# MCU.net
KiCad netlist of a schematic drawn in Altium Designer
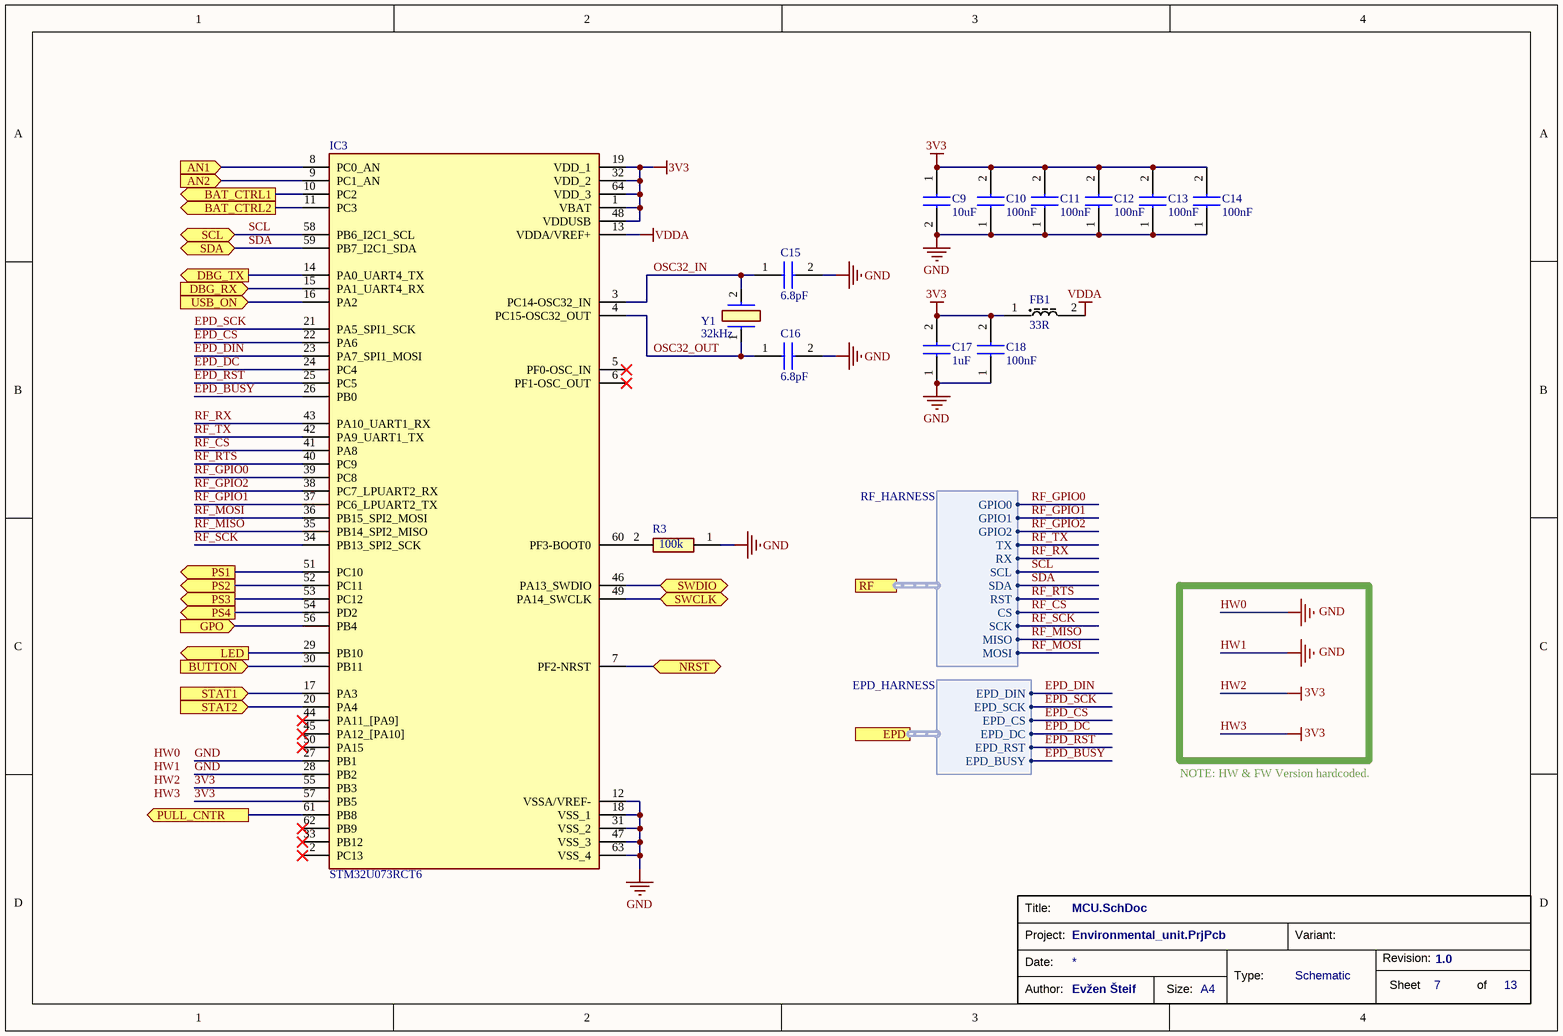
[diagram p0: MCU.SchDoc]

(export (version "E")
  (design (tool "Eeschema 10.0.6"))
  (components
    (comp (ref "C9")
      (value "10uF")
      (footprint "SamacSys:GRM18x")
      (description "Capacitor")
      (fields
        (field (name "MANUFACTURER_PART_NUMBER") "GRM188R61E106KA73D")
        (field (name "MOUSER PART NUMBER") "81-GRM188R61E106KA3D")
      )
      (libsource (lib "*") (part "GRM188R61E106KA73D"))
    )
    (comp (ref "C10")
      (value "100nF")
      (footprint "SamacSys:CAPC1005X70N")
      (description "Capacitor")
      (fields
        (field (name "MANUFACTURER_PART_NUMBER") "GRM155R61A104KA01D")
        (field (name "MOUSER PART NUMBER") "81-GRM155R61A104KA01")
      )
      (libsource (lib "*") (part "GRM155R61A104KA01D"))
    )
    (comp (ref "C11")
      (value "100nF")
      (footprint "SamacSys:CAPC1005X70N")
      (description "Capacitor")
      (fields
        (field (name "MANUFACTURER_PART_NUMBER") "GRM155R61A104KA01D")
        (field (name "MOUSER PART NUMBER") "81-GRM155R61A104KA01")
      )
      (libsource (lib "*") (part "GRM155R61A104KA01D"))
    )
    (comp (ref "C12")
      (value "100nF")
      (footprint "SamacSys:CAPC1005X70N")
      (description "Capacitor")
      (fields
        (field (name "MANUFACTURER_PART_NUMBER") "GRM155R61A104KA01D")
        (field (name "MOUSER PART NUMBER") "81-GRM155R61A104KA01")
      )
      (libsource (lib "*") (part "GRM155R61A104KA01D"))
    )
    (comp (ref "C13")
      (value "100nF")
      (footprint "SamacSys:CAPC1005X70N")
      (description "Capacitor")
      (fields
        (field (name "MANUFACTURER_PART_NUMBER") "GRM155R61A104KA01D")
        (field (name "MOUSER PART NUMBER") "81-GRM155R61A104KA01")
      )
      (libsource (lib "*") (part "GRM155R61A104KA01D"))
    )
    (comp (ref "C14")
      (value "100nF")
      (footprint "SamacSys:CAPC1005X70N")
      (description "Capacitor")
      (fields
        (field (name "MANUFACTURER_PART_NUMBER") "GRM155R61A104KA01D")
        (field (name "MOUSER PART NUMBER") "81-GRM155R61A104KA01")
      )
      (libsource (lib "*") (part "GRM155R61A104KA01D"))
    )
    (comp (ref "C15")
      (value "6.8pF")
      (footprint "SamacSys:GCM155")
      (description "Capacitor")
      (fields
        (field (name "MANUFACTURER_PART_NUMBER") "GCM1555C1H6R8BA16J")
        (field (name "MOUSER PART NUMBER") "81-GCM1555C1H6R8BA6J")
      )
      (libsource (lib "*") (part "GCM1555C1H6R8BA16J"))
    )
    (comp (ref "C16")
      (value "6.8pF")
      (footprint "SamacSys:GCM155")
      (description "Capacitor")
      (fields
        (field (name "MANUFACTURER_PART_NUMBER") "GCM1555C1H6R8BA16J")
        (field (name "MOUSER PART NUMBER") "81-GCM1555C1H6R8BA6J")
      )
      (libsource (lib "*") (part "GCM1555C1H6R8BA16J"))
    )
    (comp (ref "C17")
      (value "1uF")
      (footprint "SamacSys:CAPC1608X90N")
      (description "Capacitor")
      (fields
        (field (name "MANUFACTURER_PART_NUMBER") "GRM188R61A105KA61D")
        (field (name "MOUSER PART NUMBER") "81-GRM39R105K10")
      )
      (libsource (lib "*") (part "GRM188R61A105KA61D"))
    )
    (comp (ref "C18")
      (value "100nF")
      (footprint "SamacSys:CAPC1005X70N")
      (description "Capacitor")
      (fields
        (field (name "MANUFACTURER_PART_NUMBER") "GRM155R61A104KA01D")
        (field (name "MOUSER PART NUMBER") "81-GRM155R61A104KA01")
      )
      (libsource (lib "*") (part "GRM155R61A104KA01D"))
    )
    (comp (ref "FB1")
      (value "33R")
      (footprint "SamacSys:BLM18SP221SN1B")
      (description "Ferrite Bead")
      (fields
        (field (name "MANUFACTURER_PART_NUMBER") "BLM18SG330SN1D")
        (field (name "MOUSER PART NUMBER") "81-BLM18SG330SN1D")
      )
      (libsource (lib "SamacSys") (part "BLM18SG330SN1D"))
    )
    (comp (ref "IC3")
      (value "STM32U073RCT6")
      (footprint "SamacSys:QFP50P1200X1200X160-64N")
      (description "Integrated Circuit")
      (libsource (lib "SamacSys") (part "STM32U073RCT6"))
    )
    (comp (ref "R3")
      (value "100k")
      (footprint "SamacSys:RESC1005X35N")
      (description "Resistor")
      (fields
        (field (name "MANUFACTURER_PART_NUMBER") "RT0402FRE07100KL")
        (field (name "MOUSER PART NUMBER") "603-RT0402FRE07100KL")
      )
      (libsource (lib "*") (part "RT0402FRE07100KL"))
    )
    (comp (ref "Y1")
      (value "32kHz")
      (footprint "SamacSys:ECS32712534RRTR")
      (description "Crystal or Oscillator")
      (fields
        (field (name "MANUFACTURER_PART_NUMBER") "ECS-.327-6-34RR-TR")
        (field (name "MOUSER PART NUMBER") "520-.327-6-34RRT")
      )
      (libsource (lib "*") (part "ECS-.327-6-34RR-TR"))
    )
  )
  (nets
    (net (code "3") (name "/AN1") (class "Default")
      (node (ref "IC3") (pin "8") (pinfunction "PC0_AN_8") (pintype "passive"))
    )
    (net (code "4") (name "/AN2") (class "Default")
      (node (ref "IC3") (pin "9") (pinfunction "PC1_AN_9") (pintype "passive"))
    )
    (net (code "5") (name "/BAT_CTRL1") (class "Default")
      (node (ref "IC3") (pin "10") (pinfunction "PC2_10") (pintype "passive"))
    )
    (net (code "6") (name "/BAT_CTRL2") (class "Default")
      (node (ref "IC3") (pin "11") (pinfunction "PC3_11") (pintype "passive"))
    )
    (net (code "7") (name "/BUTTON") (class "Default")
      (node (ref "IC3") (pin "30") (pinfunction "PB11_30") (pintype "passive"))
    )
    (net (code "8") (name "/DBG_RX") (class "Default")
      (node (ref "IC3") (pin "15") (pinfunction "PA1_UART4_RX_15") (pintype "passive"))
    )
    (net (code "9") (name "/DBG_TX") (class "Default")
      (node (ref "IC3") (pin "14") (pinfunction "PA0_UART4_TX_14") (pintype "passive"))
    )
    (net (code "10") (name "/EPD_BUSY") (class "Default")
      (node (ref "IC3") (pin "26") (pinfunction "PB0_26") (pintype "passive"))
    )
    (net (code "11") (name "/EPD_CS") (class "Default")
      (node (ref "IC3") (pin "22") (pinfunction "PA6_22") (pintype "passive"))
    )
    (net (code "12") (name "/EPD_DC") (class "Default")
      (node (ref "IC3") (pin "24") (pinfunction "PC4_24") (pintype "passive"))
    )
    (net (code "13") (name "/EPD_DIN") (class "Default")
      (node (ref "IC3") (pin "23") (pinfunction "PA7_SPI1_MOSI_23") (pintype "passive"))
    )
    (net (code "14") (name "/EPD_RST") (class "Default")
      (node (ref "IC3") (pin "25") (pinfunction "PC5_25") (pintype "passive"))
    )
    (net (code "15") (name "/EPD_SCK") (class "Default")
      (node (ref "IC3") (pin "21") (pinfunction "PA5_SPI1_SCK_21") (pintype "passive"))
    )
    (net (code "16") (name "/GPO") (class "Default")
      (node (ref "IC3") (pin "56") (pinfunction "PB4_56") (pintype "passive"))
    )
    (net (code "17") (name "/LED") (class "Default")
      (node (ref "IC3") (pin "29") (pinfunction "PB10_29") (pintype "passive"))
    )
    (net (code "18") (name "/NRST") (class "Default")
      (node (ref "IC3") (pin "7") (pinfunction "PF2-NRST_7") (pintype "passive"))
    )
    (net (code "19") (name "/OSC32_IN") (class "Default")
      (node (ref "C15") (pin "1") (pinfunction "1_1") (pintype "passive"))
      (node (ref "IC3") (pin "3") (pinfunction "PC14-OSC32_IN_3") (pintype "passive"))
      (node (ref "Y1") (pin "2") (pinfunction "2_2") (pintype "passive"))
    )
    (net (code "20") (name "/OSC32_OUT") (class "Default")
      (node (ref "C16") (pin "1") (pinfunction "1_1") (pintype "passive"))
      (node (ref "IC3") (pin "4") (pinfunction "PC15-OSC32_OUT_4") (pintype "passive"))
      (node (ref "Y1") (pin "1") (pinfunction "1_1") (pintype "passive"))
    )
    (net (code "21") (name "/PS1") (class "Default")
      (node (ref "IC3") (pin "51") (pinfunction "PC10_51") (pintype "passive"))
    )
    (net (code "22") (name "/PS2") (class "Default")
      (node (ref "IC3") (pin "52") (pinfunction "PC11_52") (pintype "passive"))
    )
    (net (code "23") (name "/PS3") (class "Default")
      (node (ref "IC3") (pin "53") (pinfunction "PC12_53") (pintype "passive"))
    )
    (net (code "24") (name "/PS4") (class "Default")
      (node (ref "IC3") (pin "54") (pinfunction "PD2_54") (pintype "passive"))
    )
    (net (code "25") (name "/PULL_CNTR") (class "Default")
      (node (ref "IC3") (pin "61") (pinfunction "PB8_61") (pintype "passive"))
    )
    (net (code "26") (name "/RF_CS") (class "Default")
      (node (ref "IC3") (pin "41") (pinfunction "PA8_41") (pintype "passive"))
    )
    (net (code "27") (name "/RF_GPIO0") (class "Default")
      (node (ref "IC3") (pin "39") (pinfunction "PC8_39") (pintype "passive"))
    )
    (net (code "28") (name "/RF_GPIO1") (class "Default")
      (node (ref "IC3") (pin "37") (pinfunction "PC6_LPUART2_TX_37") (pintype "passive"))
    )
    (net (code "29") (name "/RF_GPIO2") (class "Default")
      (node (ref "IC3") (pin "38") (pinfunction "PC7_LPUART2_RX_38") (pintype "passive"))
    )
    (net (code "30") (name "/RF_MISO") (class "Default")
      (node (ref "IC3") (pin "35") (pinfunction "PB14_SPI2_MISO_35") (pintype "passive"))
    )
    (net (code "31") (name "/RF_MOSI") (class "Default")
      (node (ref "IC3") (pin "36") (pinfunction "PB15_SPI2_MOSI_36") (pintype "passive"))
    )
    (net (code "32") (name "/RF_RTS") (class "Default")
      (node (ref "IC3") (pin "40") (pinfunction "PC9_40") (pintype "passive"))
    )
    (net (code "33") (name "/RF_RX") (class "Default")
      (node (ref "IC3") (pin "43") (pinfunction "PA10_UART1_RX_43") (pintype "passive"))
    )
    (net (code "34") (name "/RF_SCK") (class "Default")
      (node (ref "IC3") (pin "34") (pinfunction "PB13_SPI2_SCK_34") (pintype "passive"))
    )
    (net (code "35") (name "/RF_TX") (class "Default")
      (node (ref "IC3") (pin "42") (pinfunction "PA9_UART1_TX_42") (pintype "passive"))
    )
    (net (code "36") (name "/SCL") (class "Default")
      (node (ref "IC3") (pin "58") (pinfunction "PB6_I2C1_SCL_58") (pintype "passive"))
    )
    (net (code "37") (name "/SDA") (class "Default")
      (node (ref "IC3") (pin "59") (pinfunction "PB7_I2C1_SDA_59") (pintype "passive"))
    )
    (net (code "38") (name "/STAT1") (class "Default")
      (node (ref "IC3") (pin "17") (pinfunction "PA3_17") (pintype "passive"))
    )
    (net (code "39") (name "/STAT2") (class "Default")
      (node (ref "IC3") (pin "20") (pinfunction "PA4_20") (pintype "passive"))
    )
    (net (code "40") (name "/SWCLK") (class "Default")
      (node (ref "IC3") (pin "49") (pinfunction "PA14_SWCLK_49") (pintype "passive"))
    )
    (net (code "41") (name "/SWDIO") (class "Default")
      (node (ref "IC3") (pin "46") (pinfunction "PA13_SWDIO_46") (pintype "passive"))
    )
    (net (code "42") (name "/USB_ON") (class "Default")
      (node (ref "IC3") (pin "16") (pinfunction "PA2_16") (pintype "passive"))
    )
    (net (code "45") (name "3V3") (class "Default")
      (node (ref "C10") (pin "2") (pinfunction "2_2") (pintype "passive"))
      (node (ref "C11") (pin "2") (pinfunction "2_2") (pintype "passive"))
      (node (ref "C12") (pin "2") (pinfunction "2_2") (pintype "passive"))
      (node (ref "C13") (pin "2") (pinfunction "2_2") (pintype "passive"))
      (node (ref "C14") (pin "2") (pinfunction "2_2") (pintype "passive"))
      (node (ref "C17") (pin "2") (pinfunction "2_2") (pintype "passive"))
      (node (ref "C18") (pin "2") (pinfunction "2_2") (pintype "passive"))
      (node (ref "C9") (pin "1") (pinfunction "1_1") (pintype "passive"))
      (node (ref "FB1") (pin "1") (pinfunction "1_1") (pintype "passive"))
      (node (ref "IC3") (pin "1") (pinfunction "VBAT_1") (pintype "passive"))
      (node (ref "IC3") (pin "19") (pinfunction "VDD_1_19") (pintype "passive"))
      (node (ref "IC3") (pin "32") (pinfunction "VDD_2_32") (pintype "passive"))
      (node (ref "IC3") (pin "48") (pinfunction "VDDUSB_48") (pintype "passive"))
      (node (ref "IC3") (pin "55") (pinfunction "PB3_55") (pintype "passive"))
      (node (ref "IC3") (pin "57") (pinfunction "PB5_57") (pintype "passive"))
      (node (ref "IC3") (pin "64") (pinfunction "VDD_3_64") (pintype "passive"))
    )
    (net (code "46") (name "GND") (class "Default")
      (node (ref "C10") (pin "1") (pinfunction "1_1") (pintype "passive"))
      (node (ref "C11") (pin "1") (pinfunction "1_1") (pintype "passive"))
      (node (ref "C12") (pin "1") (pinfunction "1_1") (pintype "passive"))
      (node (ref "C13") (pin "1") (pinfunction "1_1") (pintype "passive"))
      (node (ref "C14") (pin "1") (pinfunction "1_1") (pintype "passive"))
      (node (ref "C15") (pin "2") (pinfunction "2_2") (pintype "passive"))
      (node (ref "C16") (pin "2") (pinfunction "2_2") (pintype "passive"))
      (node (ref "C17") (pin "1") (pinfunction "1_1") (pintype "passive"))
      (node (ref "C18") (pin "1") (pinfunction "1_1") (pintype "passive"))
      (node (ref "C9") (pin "2") (pinfunction "2_2") (pintype "passive"))
      (node (ref "IC3") (pin "12") (pinfunction "VSSA/VREF-_12") (pintype "passive"))
      (node (ref "IC3") (pin "18") (pinfunction "VSS_1_18") (pintype "passive"))
      (node (ref "IC3") (pin "27") (pinfunction "PB1_27") (pintype "passive"))
      (node (ref "IC3") (pin "28") (pinfunction "PB2_28") (pintype "passive"))
      (node (ref "IC3") (pin "31") (pinfunction "VSS_2_31") (pintype "passive"))
      (node (ref "IC3") (pin "47") (pinfunction "VSS_3_47") (pintype "passive"))
      (node (ref "IC3") (pin "63") (pinfunction "VSS_4_63") (pintype "passive"))
      (node (ref "R3") (pin "1") (pinfunction "1_1") (pintype "passive"))
    )
    (net (code "47") (name "Net-(IC3-PF3-BOOT0)") (class "Default")
      (node (ref "IC3") (pin "60") (pinfunction "PF3-BOOT0_60") (pintype "passive"))
      (node (ref "R3") (pin "2") (pinfunction "2_2") (pintype "passive"))
    )
    (net (code "48") (name "VDDA") (class "Default")
      (node (ref "FB1") (pin "2") (pinfunction "2_2") (pintype "passive"))
      (node (ref "IC3") (pin "13") (pinfunction "VDDA/VREF+_13") (pintype "passive"))
    )
    (net (code "49") (name "unconnected-(IC3-PA11_[PA9]-Pad44)") (class "Default")
      (node (ref "IC3") (pin "44") (pinfunction "PA11_[PA9]_44") (pintype "passive+no_connect"))
    )
    (net (code "50") (name "unconnected-(IC3-PA12_[PA10]-Pad45)") (class "Default")
      (node (ref "IC3") (pin "45") (pinfunction "PA12_[PA10]_45") (pintype "passive+no_connect"))
    )
    (net (code "51") (name "unconnected-(IC3-PA15-Pad50)") (class "Default")
      (node (ref "IC3") (pin "50") (pinfunction "PA15_50") (pintype "passive+no_connect"))
    )
    (net (code "52") (name "unconnected-(IC3-PB9-Pad62)") (class "Default")
      (node (ref "IC3") (pin "62") (pinfunction "PB9_62") (pintype "passive+no_connect"))
    )
    (net (code "53") (name "unconnected-(IC3-PB12-Pad33)") (class "Default")
      (node (ref "IC3") (pin "33") (pinfunction "PB12_33") (pintype "passive+no_connect"))
    )
    (net (code "54") (name "unconnected-(IC3-PC13-Pad2)") (class "Default")
      (node (ref "IC3") (pin "2") (pinfunction "PC13_2") (pintype "passive+no_connect"))
    )
    (net (code "55") (name "unconnected-(IC3-PF0-OSC_IN-Pad5)") (class "Default")
      (node (ref "IC3") (pin "5") (pinfunction "PF0-OSC_IN_5") (pintype "passive+no_connect"))
    )
    (net (code "56") (name "unconnected-(IC3-PF1-OSC_OUT-Pad6)") (class "Default")
      (node (ref "IC3") (pin "6") (pinfunction "PF1-OSC_OUT_6") (pintype "passive+no_connect"))
    )
  )
)
